# display_driver.net
KiCad netlist of a schematic drawn in EAGLE
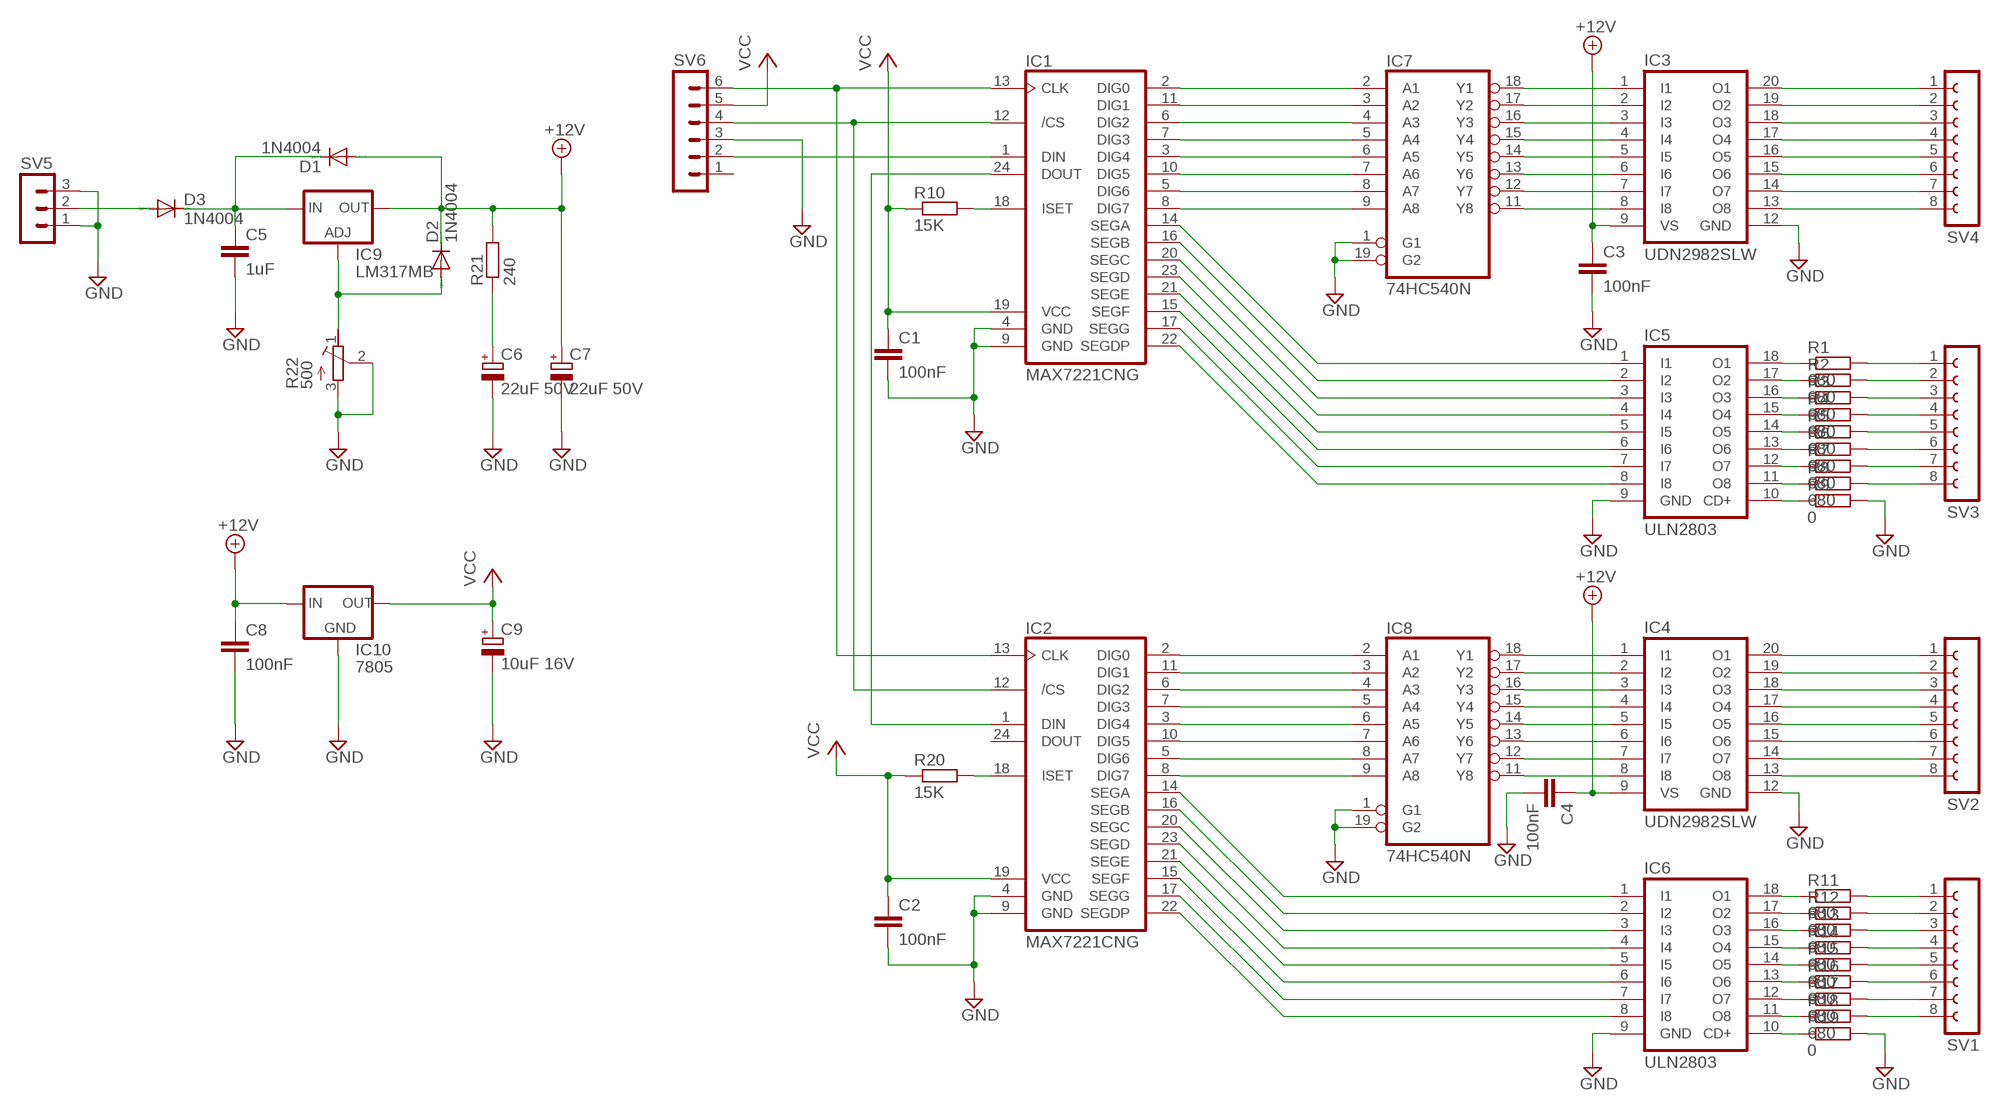
[diagram p0: schematic, sheet 1]

(export (version "E")
  (design (tool "Eeschema 10.0.6"))
  (components
    (comp (ref "C1")
      (value "100nF")
      (footprint "eagle-import:C5B2.5")
      (libsource (lib "eagle-import") (part "C5/2.5"))
    )
    (comp (ref "C2")
      (value "100nF")
      (footprint "eagle-import:C5B2.5")
      (libsource (lib "eagle-import") (part "C5/2.5"))
    )
    (comp (ref "C3")
      (value "100nF")
      (footprint "eagle-import:C5B2.5")
      (libsource (lib "eagle-import") (part "C5/2.5"))
    )
    (comp (ref "C4")
      (value "100nF")
      (footprint "eagle-import:C5B2.5")
      (libsource (lib "eagle-import") (part "C5/2.5"))
    )
    (comp (ref "C5")
      (value "1uF")
      (footprint "eagle-import:C5B2.5")
      (libsource (lib "eagle-import") (part "C5/2.5"))
    )
    (comp (ref "C6")
      (value "22uF 50V")
      (footprint "eagle-import:E3,5-8")
      (libsource (lib "eagle-import") (part "CPOL-EUE3.5-8"))
    )
    (comp (ref "C7")
      (value "22uF 50V")
      (footprint "eagle-import:E3,5-8")
      (libsource (lib "eagle-import") (part "CPOL-EUE3.5-8"))
    )
    (comp (ref "C8")
      (value "100nF")
      (footprint "eagle-import:C5B2.5")
      (libsource (lib "eagle-import") (part "C5/2.5"))
    )
    (comp (ref "C9")
      (value "10uF 16V")
      (footprint "eagle-import:E3,5-8")
      (libsource (lib "eagle-import") (part "CPOL-EUE3.5-8"))
    )
    (comp (ref "D1")
      (value "1N4004")
      (footprint "eagle-import:DO41-10")
      (libsource (lib "eagle-import") (part "1N4004"))
    )
    (comp (ref "D2")
      (value "1N4004")
      (footprint "eagle-import:DO41-10")
      (libsource (lib "eagle-import") (part "1N4004"))
    )
    (comp (ref "D3")
      (value "1N4004")
      (footprint "eagle-import:DO41-10")
      (libsource (lib "eagle-import") (part "1N4004"))
    )
    (comp (ref "IC1")
      (value "MAX7221CNG")
      (footprint "eagle-import:DIL24-3")
      (libsource (lib "eagle-import") (part "MAX7221NGC"))
    )
    (comp (ref "IC2")
      (value "MAX7221CNG")
      (footprint "eagle-import:DIL24-3")
      (libsource (lib "eagle-import") (part "MAX7221NGC"))
    )
    (comp (ref "IC3")
      (value "UDN2982SLW")
      (footprint "eagle-import:SO20W")
      (libsource (lib "eagle-import") (part "UDN298SLW2"))
    )
    (comp (ref "IC4")
      (value "UDN2982SLW")
      (footprint "eagle-import:SO20W")
      (libsource (lib "eagle-import") (part "UDN298SLW2"))
    )
    (comp (ref "IC5")
      (value "ULN2803")
      (footprint "eagle-import:DIL18")
      (libsource (lib "eagle-import") (part "ULN2803A"))
    )
    (comp (ref "IC6")
      (value "ULN2803")
      (footprint "eagle-import:DIL18")
      (libsource (lib "eagle-import") (part "ULN2803A"))
    )
    (comp (ref "IC7")
      (value "74HC540N")
      (footprint "eagle-import:DIL20")
      (libsource (lib "eagle-import") (part "74540NHC"))
    )
    (comp (ref "IC8")
      (value "74HC540N")
      (footprint "eagle-import:DIL20")
      (libsource (lib "eagle-import") (part "74540NHC"))
    )
    (comp (ref "IC9")
      (value "LM317MB")
      (footprint "eagle-import:TO220L1")
      (libsource (lib "eagle-import") (part "LM317?MB"))
    )
    (comp (ref "IC10")
      (value "7805")
      (footprint "eagle-import:78XXL")
      (libsource (lib "eagle-import") (part "78XXL"))
    )
    (comp (ref "R1")
      (value "680")
      (footprint "eagle-import:0207_10")
      (libsource (lib "eagle-import") (part "R-EU_0207/10"))
    )
    (comp (ref "R2")
      (value "680")
      (footprint "eagle-import:0207_10")
      (libsource (lib "eagle-import") (part "R-EU_0207/10"))
    )
    (comp (ref "R3")
      (value "680")
      (footprint "eagle-import:0207_10")
      (libsource (lib "eagle-import") (part "R-EU_0207/10"))
    )
    (comp (ref "R4")
      (value "680")
      (footprint "eagle-import:0207_10")
      (libsource (lib "eagle-import") (part "R-EU_0207/10"))
    )
    (comp (ref "R5")
      (value "680")
      (footprint "eagle-import:0207_10")
      (libsource (lib "eagle-import") (part "R-EU_0207/10"))
    )
    (comp (ref "R6")
      (value "680")
      (footprint "eagle-import:0207_10")
      (libsource (lib "eagle-import") (part "R-EU_0207/10"))
    )
    (comp (ref "R7")
      (value "680")
      (footprint "eagle-import:0207_10")
      (libsource (lib "eagle-import") (part "R-EU_0207/10"))
    )
    (comp (ref "R8")
      (value "680")
      (footprint "eagle-import:0207_10")
      (libsource (lib "eagle-import") (part "R-EU_0207/10"))
    )
    (comp (ref "R9")
      (value "0")
      (footprint "eagle-import:0207_10")
      (libsource (lib "eagle-import") (part "R-EU_0207/10"))
    )
    (comp (ref "R10")
      (value "15K")
      (footprint "eagle-import:0207_10")
      (libsource (lib "eagle-import") (part "R-EU_0207/10"))
    )
    (comp (ref "R11")
      (value "680")
      (footprint "eagle-import:0207_10")
      (libsource (lib "eagle-import") (part "R-EU_0207/10"))
    )
    (comp (ref "R12")
      (value "680")
      (footprint "eagle-import:0207_10")
      (libsource (lib "eagle-import") (part "R-EU_0207/10"))
    )
    (comp (ref "R13")
      (value "680")
      (footprint "eagle-import:0207_10")
      (libsource (lib "eagle-import") (part "R-EU_0207/10"))
    )
    (comp (ref "R14")
      (value "680")
      (footprint "eagle-import:0207_10")
      (libsource (lib "eagle-import") (part "R-EU_0207/10"))
    )
    (comp (ref "R15")
      (value "680")
      (footprint "eagle-import:0207_10")
      (libsource (lib "eagle-import") (part "R-EU_0207/10"))
    )
    (comp (ref "R16")
      (value "680")
      (footprint "eagle-import:0207_10")
      (libsource (lib "eagle-import") (part "R-EU_0207/10"))
    )
    (comp (ref "R17")
      (value "680")
      (footprint "eagle-import:0207_10")
      (libsource (lib "eagle-import") (part "R-EU_0207/10"))
    )
    (comp (ref "R18")
      (value "680")
      (footprint "eagle-import:0207_10")
      (libsource (lib "eagle-import") (part "R-EU_0207/10"))
    )
    (comp (ref "R19")
      (value "0")
      (footprint "eagle-import:0207_10")
      (libsource (lib "eagle-import") (part "R-EU_0207/10"))
    )
    (comp (ref "R20")
      (value "15K")
      (footprint "eagle-import:0207_10")
      (libsource (lib "eagle-import") (part "R-EU_0207/10"))
    )
    (comp (ref "R21")
      (value "240")
      (footprint "eagle-import:0207_10")
      (libsource (lib "eagle-import") (part "R-EU_0207/10"))
    )
    (comp (ref "R22")
      (value "500")
      (footprint "eagle-import:RTRIMT93YA")
      (libsource (lib "eagle-import") (part "R-TRIMMT93YA"))
    )
    (comp (ref "SV1")
      (value "FE08-1")
      (footprint "eagle-import:FE08")
      (libsource (lib "eagle-import") (part "FE08-1"))
    )
    (comp (ref "SV2")
      (value "FE08-1")
      (footprint "eagle-import:FE08")
      (libsource (lib "eagle-import") (part "FE08-1"))
    )
    (comp (ref "SV3")
      (value "FE08-1")
      (footprint "eagle-import:FE08")
      (libsource (lib "eagle-import") (part "FE08-1"))
    )
    (comp (ref "SV4")
      (value "FE08-1")
      (footprint "eagle-import:FE08")
      (libsource (lib "eagle-import") (part "FE08-1"))
    )
    (comp (ref "SV5")
      (value "MA03-1")
      (footprint "eagle-import:MA03-1")
      (libsource (lib "eagle-import") (part "MA03-1"))
    )
    (comp (ref "SV6")
      (value "MA06-1")
      (footprint "eagle-import:MA06-1")
      (libsource (lib "eagle-import") (part "MA06-1"))
    )
  )
  (nets
    (net (code "1") (name "+12V") (class "Default")
      (node (ref "C3") (pin "1") (pinfunction "1_1") (pintype "passive"))
      (node (ref "C4") (pin "1") (pinfunction "1_1") (pintype "passive"))
      (node (ref "C7") (pin "+") (pinfunction "+_+") (pintype "passive"))
      (node (ref "C8") (pin "1") (pinfunction "1_1") (pintype "passive"))
      (node (ref "D1") (pin "A") (pinfunction "A_A") (pintype "passive"))
      (node (ref "D2") (pin "C") (pinfunction "C_C") (pintype "passive"))
      (node (ref "IC10") (pin "IN") (pinfunction "IN_IN") (pintype "input"))
      (node (ref "IC3") (pin "9") (pinfunction "VS_9") (pintype "passive"))
      (node (ref "IC4") (pin "9") (pinfunction "VS_9") (pintype "passive"))
      (node (ref "IC9") (pin "2") (pinfunction "OUT_2") (pintype "passive"))
      (node (ref "R21") (pin "2") (pinfunction "2_2") (pintype "passive"))
    )
    (net (code "2") (name "GND") (class "Default")
      (node (ref "C1") (pin "2") (pinfunction "2_2") (pintype "passive"))
      (node (ref "C2") (pin "2") (pinfunction "2_2") (pintype "passive"))
      (node (ref "C3") (pin "2") (pinfunction "2_2") (pintype "passive"))
      (node (ref "C4") (pin "2") (pinfunction "2_2") (pintype "passive"))
      (node (ref "C5") (pin "2") (pinfunction "2_2") (pintype "passive"))
      (node (ref "C6") (pin "-") (pinfunction "-_-") (pintype "passive"))
      (node (ref "C7") (pin "-") (pinfunction "-_-") (pintype "passive"))
      (node (ref "C8") (pin "2") (pinfunction "2_2") (pintype "passive"))
      (node (ref "C9") (pin "-") (pinfunction "-_-") (pintype "passive"))
      (node (ref "IC1") (pin "4") (pinfunction "GND_4") (pintype "power_in"))
      (node (ref "IC1") (pin "9") (pinfunction "GND_9") (pintype "power_in"))
      (node (ref "IC10") (pin "GND") (pinfunction "GND_GND") (pintype "input"))
      (node (ref "IC2") (pin "4") (pinfunction "GND_4") (pintype "power_in"))
      (node (ref "IC2") (pin "9") (pinfunction "GND_9") (pintype "power_in"))
      (node (ref "IC3") (pin "12") (pinfunction "GND_12") (pintype "power_in"))
      (node (ref "IC4") (pin "12") (pinfunction "GND_12") (pintype "power_in"))
      (node (ref "IC5") (pin "9") (pinfunction "GND_9") (pintype "power_in"))
      (node (ref "IC6") (pin "9") (pinfunction "GND_9") (pintype "power_in"))
      (node (ref "IC7") (pin "1") (pinfunction "G1_1") (pintype "input"))
      (node (ref "IC7") (pin "19") (pinfunction "G2_19") (pintype "input"))
      (node (ref "IC8") (pin "1") (pinfunction "G1_1") (pintype "input"))
      (node (ref "IC8") (pin "19") (pinfunction "G2_19") (pintype "input"))
      (node (ref "R19") (pin "2") (pinfunction "2_2") (pintype "passive"))
      (node (ref "R22") (pin "2") (pinfunction "S_2") (pintype "passive"))
      (node (ref "R22") (pin "3") (pinfunction "A_3") (pintype "passive"))
      (node (ref "R9") (pin "2") (pinfunction "2_2") (pintype "passive"))
      (node (ref "SV5") (pin "1") (pinfunction "1_1") (pintype "passive"))
      (node (ref "SV5") (pin "3") (pinfunction "3_3") (pintype "passive"))
      (node (ref "SV6") (pin "3") (pinfunction "3_3") (pintype "passive"))
    )
    (net (code "3") (name "Net-(C6-Pad+)") (class "Default")
      (node (ref "C6") (pin "+") (pinfunction "+_+") (pintype "passive"))
      (node (ref "R21") (pin "1") (pinfunction "1_1") (pintype "passive"))
    )
    (net (code "4") (name "Net-(D3-PadA)") (class "Default")
      (node (ref "D3") (pin "A") (pinfunction "A_A") (pintype "passive"))
      (node (ref "SV5") (pin "2") (pinfunction "2_2") (pintype "passive"))
    )
    (net (code "5") (name "Net-(IC1-CLK)") (class "Default")
      (node (ref "IC1") (pin "13") (pinfunction "CLK_13") (pintype "input"))
      (node (ref "IC2") (pin "13") (pinfunction "CLK_13") (pintype "input"))
      (node (ref "SV6") (pin "6") (pinfunction "6_6") (pintype "passive"))
    )
    (net (code "6") (name "Net-(IC1-DIG0)") (class "Default")
      (node (ref "IC1") (pin "2") (pinfunction "DIG0_2") (pintype "open_collector"))
      (node (ref "IC7") (pin "2") (pinfunction "A1_2") (pintype "input"))
    )
    (net (code "7") (name "Net-(IC1-DIG1)") (class "Default")
      (node (ref "IC1") (pin "11") (pinfunction "DIG1_11") (pintype "open_collector"))
      (node (ref "IC7") (pin "3") (pinfunction "A2_3") (pintype "input"))
    )
    (net (code "8") (name "Net-(IC1-DIG2)") (class "Default")
      (node (ref "IC1") (pin "6") (pinfunction "DIG2_6") (pintype "open_collector"))
      (node (ref "IC7") (pin "4") (pinfunction "A3_4") (pintype "input"))
    )
    (net (code "9") (name "Net-(IC1-DIG3)") (class "Default")
      (node (ref "IC1") (pin "7") (pinfunction "DIG3_7") (pintype "open_collector"))
      (node (ref "IC7") (pin "5") (pinfunction "A4_5") (pintype "input"))
    )
    (net (code "10") (name "Net-(IC1-DIG4)") (class "Default")
      (node (ref "IC1") (pin "3") (pinfunction "DIG4_3") (pintype "open_collector"))
      (node (ref "IC7") (pin "6") (pinfunction "A5_6") (pintype "input"))
    )
    (net (code "11") (name "Net-(IC1-DIG5)") (class "Default")
      (node (ref "IC1") (pin "10") (pinfunction "DIG5_10") (pintype "open_collector"))
      (node (ref "IC7") (pin "7") (pinfunction "A6_7") (pintype "input"))
    )
    (net (code "12") (name "Net-(IC1-DIG6)") (class "Default")
      (node (ref "IC1") (pin "5") (pinfunction "DIG6_5") (pintype "open_collector"))
      (node (ref "IC7") (pin "8") (pinfunction "A7_8") (pintype "input"))
    )
    (net (code "13") (name "Net-(IC1-DIG7)") (class "Default")
      (node (ref "IC1") (pin "8") (pinfunction "DIG7_8") (pintype "open_collector"))
      (node (ref "IC7") (pin "9") (pinfunction "A8_9") (pintype "input"))
    )
    (net (code "14") (name "Net-(IC1-DIN)") (class "Default")
      (node (ref "IC1") (pin "1") (pinfunction "DIN_1") (pintype "input"))
      (node (ref "SV6") (pin "2") (pinfunction "2_2") (pintype "passive"))
    )
    (net (code "15") (name "Net-(IC1-DOUT)") (class "Default")
      (node (ref "IC1") (pin "24") (pinfunction "DOUT_24") (pintype "output"))
      (node (ref "IC2") (pin "1") (pinfunction "DIN_1") (pintype "input"))
    )
    (net (code "16") (name "Net-(IC1-ISET)") (class "Default")
      (node (ref "IC1") (pin "18") (pinfunction "ISET_18") (pintype "input"))
      (node (ref "R10") (pin "2") (pinfunction "2_2") (pintype "passive"))
    )
    (net (code "17") (name "Net-(IC1-SEGA)") (class "Default")
      (node (ref "IC1") (pin "14") (pinfunction "SEGA_14") (pintype "output"))
      (node (ref "IC5") (pin "1") (pinfunction "I1_1") (pintype "input"))
    )
    (net (code "18") (name "Net-(IC1-SEGB)") (class "Default")
      (node (ref "IC1") (pin "16") (pinfunction "SEGB_16") (pintype "output"))
      (node (ref "IC5") (pin "2") (pinfunction "I2_2") (pintype "input"))
    )
    (net (code "19") (name "Net-(IC1-SEGC)") (class "Default")
      (node (ref "IC1") (pin "20") (pinfunction "SEGC_20") (pintype "output"))
      (node (ref "IC5") (pin "3") (pinfunction "I3_3") (pintype "input"))
    )
    (net (code "20") (name "Net-(IC1-SEGD)") (class "Default")
      (node (ref "IC1") (pin "23") (pinfunction "SEGD_23") (pintype "output"))
      (node (ref "IC5") (pin "4") (pinfunction "I4_4") (pintype "input"))
    )
    (net (code "21") (name "Net-(IC1-SEGDP)") (class "Default")
      (node (ref "IC1") (pin "22") (pinfunction "SEGDP_22") (pintype "output"))
      (node (ref "IC5") (pin "8") (pinfunction "I8_8") (pintype "input"))
    )
    (net (code "22") (name "Net-(IC1-SEGE)") (class "Default")
      (node (ref "IC1") (pin "21") (pinfunction "SEGE_21") (pintype "output"))
      (node (ref "IC5") (pin "5") (pinfunction "I5_5") (pintype "input"))
    )
    (net (code "23") (name "Net-(IC1-SEGF)") (class "Default")
      (node (ref "IC1") (pin "15") (pinfunction "SEGF_15") (pintype "output"))
      (node (ref "IC5") (pin "6") (pinfunction "I6_6") (pintype "input"))
    )
    (net (code "24") (name "Net-(IC1-SEGG)") (class "Default")
      (node (ref "IC1") (pin "17") (pinfunction "SEGG_17") (pintype "output"))
      (node (ref "IC5") (pin "7") (pinfunction "I7_7") (pintype "input"))
    )
    (net (code "25") (name "Net-(IC1-{slash}CS)") (class "Default")
      (node (ref "IC1") (pin "12") (pinfunction "/CS_12") (pintype "input"))
      (node (ref "IC2") (pin "12") (pinfunction "/CS_12") (pintype "input"))
      (node (ref "SV6") (pin "4") (pinfunction "4_4") (pintype "passive"))
    )
    (net (code "26") (name "Net-(IC2-DIG0)") (class "Default")
      (node (ref "IC2") (pin "2") (pinfunction "DIG0_2") (pintype "open_collector"))
      (node (ref "IC8") (pin "2") (pinfunction "A1_2") (pintype "input"))
    )
    (net (code "27") (name "Net-(IC2-DIG1)") (class "Default")
      (node (ref "IC2") (pin "11") (pinfunction "DIG1_11") (pintype "open_collector"))
      (node (ref "IC8") (pin "3") (pinfunction "A2_3") (pintype "input"))
    )
    (net (code "28") (name "Net-(IC2-DIG2)") (class "Default")
      (node (ref "IC2") (pin "6") (pinfunction "DIG2_6") (pintype "open_collector"))
      (node (ref "IC8") (pin "4") (pinfunction "A3_4") (pintype "input"))
    )
    (net (code "29") (name "Net-(IC2-DIG3)") (class "Default")
      (node (ref "IC2") (pin "7") (pinfunction "DIG3_7") (pintype "open_collector"))
      (node (ref "IC8") (pin "5") (pinfunction "A4_5") (pintype "input"))
    )
    (net (code "30") (name "Net-(IC2-DIG4)") (class "Default")
      (node (ref "IC2") (pin "3") (pinfunction "DIG4_3") (pintype "open_collector"))
      (node (ref "IC8") (pin "6") (pinfunction "A5_6") (pintype "input"))
    )
    (net (code "31") (name "Net-(IC2-DIG5)") (class "Default")
      (node (ref "IC2") (pin "10") (pinfunction "DIG5_10") (pintype "open_collector"))
      (node (ref "IC8") (pin "7") (pinfunction "A6_7") (pintype "input"))
    )
    (net (code "32") (name "Net-(IC2-DIG6)") (class "Default")
      (node (ref "IC2") (pin "5") (pinfunction "DIG6_5") (pintype "open_collector"))
      (node (ref "IC8") (pin "8") (pinfunction "A7_8") (pintype "input"))
    )
    (net (code "33") (name "Net-(IC2-DIG7)") (class "Default")
      (node (ref "IC2") (pin "8") (pinfunction "DIG7_8") (pintype "open_collector"))
      (node (ref "IC8") (pin "9") (pinfunction "A8_9") (pintype "input"))
    )
    (net (code "34") (name "Net-(IC2-ISET)") (class "Default")
      (node (ref "IC2") (pin "18") (pinfunction "ISET_18") (pintype "input"))
      (node (ref "R20") (pin "2") (pinfunction "2_2") (pintype "passive"))
    )
    (net (code "35") (name "Net-(IC2-SEGA)") (class "Default")
      (node (ref "IC2") (pin "14") (pinfunction "SEGA_14") (pintype "output"))
      (node (ref "IC6") (pin "1") (pinfunction "I1_1") (pintype "input"))
    )
    (net (code "36") (name "Net-(IC2-SEGB)") (class "Default")
      (node (ref "IC2") (pin "16") (pinfunction "SEGB_16") (pintype "output"))
      (node (ref "IC6") (pin "2") (pinfunction "I2_2") (pintype "input"))
    )
    (net (code "37") (name "Net-(IC2-SEGC)") (class "Default")
      (node (ref "IC2") (pin "20") (pinfunction "SEGC_20") (pintype "output"))
      (node (ref "IC6") (pin "3") (pinfunction "I3_3") (pintype "input"))
    )
    (net (code "38") (name "Net-(IC2-SEGD)") (class "Default")
      (node (ref "IC2") (pin "23") (pinfunction "SEGD_23") (pintype "output"))
      (node (ref "IC6") (pin "4") (pinfunction "I4_4") (pintype "input"))
    )
    (net (code "39") (name "Net-(IC2-SEGDP)") (class "Default")
      (node (ref "IC2") (pin "22") (pinfunction "SEGDP_22") (pintype "output"))
      (node (ref "IC6") (pin "8") (pinfunction "I8_8") (pintype "input"))
    )
    (net (code "40") (name "Net-(IC2-SEGE)") (class "Default")
      (node (ref "IC2") (pin "21") (pinfunction "SEGE_21") (pintype "output"))
      (node (ref "IC6") (pin "5") (pinfunction "I5_5") (pintype "input"))
    )
    (net (code "41") (name "Net-(IC2-SEGF)") (class "Default")
      (node (ref "IC2") (pin "15") (pinfunction "SEGF_15") (pintype "output"))
      (node (ref "IC6") (pin "6") (pinfunction "I6_6") (pintype "input"))
    )
    (net (code "42") (name "Net-(IC2-SEGG)") (class "Default")
      (node (ref "IC2") (pin "17") (pinfunction "SEGG_17") (pintype "output"))
      (node (ref "IC6") (pin "7") (pinfunction "I7_7") (pintype "input"))
    )
    (net (code "43") (name "Net-(IC3-I1)") (class "Default")
      (node (ref "IC3") (pin "1") (pinfunction "I1_1") (pintype "input"))
      (node (ref "IC7") (pin "18") (pinfunction "Y1_18") (pintype "tri_state"))
    )
    (net (code "44") (name "Net-(IC3-I2)") (class "Default")
      (node (ref "IC3") (pin "2") (pinfunction "I2_2") (pintype "input"))
      (node (ref "IC7") (pin "17") (pinfunction "Y2_17") (pintype "tri_state"))
    )
    (net (code "45") (name "Net-(IC3-I3)") (class "Default")
      (node (ref "IC3") (pin "3") (pinfunction "I3_3") (pintype "input"))
      (node (ref "IC7") (pin "16") (pinfunction "Y3_16") (pintype "tri_state"))
    )
    (net (code "46") (name "Net-(IC3-I4)") (class "Default")
      (node (ref "IC3") (pin "4") (pinfunction "I4_4") (pintype "input"))
      (node (ref "IC7") (pin "15") (pinfunction "Y4_15") (pintype "tri_state"))
    )
    (net (code "47") (name "Net-(IC3-I5)") (class "Default")
      (node (ref "IC3") (pin "5") (pinfunction "I5_5") (pintype "input"))
      (node (ref "IC7") (pin "14") (pinfunction "Y5_14") (pintype "tri_state"))
    )
    (net (code "48") (name "Net-(IC3-I6)") (class "Default")
      (node (ref "IC3") (pin "6") (pinfunction "I6_6") (pintype "input"))
      (node (ref "IC7") (pin "13") (pinfunction "Y6_13") (pintype "tri_state"))
    )
    (net (code "49") (name "Net-(IC3-I7)") (class "Default")
      (node (ref "IC3") (pin "7") (pinfunction "I7_7") (pintype "input"))
      (node (ref "IC7") (pin "12") (pinfunction "Y7_12") (pintype "tri_state"))
    )
    (net (code "50") (name "Net-(IC3-I8)") (class "Default")
      (node (ref "IC3") (pin "8") (pinfunction "I8_8") (pintype "input"))
      (node (ref "IC7") (pin "11") (pinfunction "Y8_11") (pintype "tri_state"))
    )
    (net (code "51") (name "Net-(IC3-O1)") (class "Default")
      (node (ref "IC3") (pin "20") (pinfunction "O1_20") (pintype "open_collector"))
      (node (ref "SV4") (pin "1") (pinfunction "1_1") (pintype "passive"))
    )
    (net (code "52") (name "Net-(IC3-O2)") (class "Default")
      (node (ref "IC3") (pin "19") (pinfunction "O2_19") (pintype "open_collector"))
      (node (ref "SV4") (pin "2") (pinfunction "2_2") (pintype "passive"))
    )
    (net (code "53") (name "Net-(IC3-O3)") (class "Default")
      (node (ref "IC3") (pin "18") (pinfunction "O3_18") (pintype "open_collector"))
      (node (ref "SV4") (pin "3") (pinfunction "3_3") (pintype "passive"))
    )
    (net (code "54") (name "Net-(IC3-O4)") (class "Default")
      (node (ref "IC3") (pin "17") (pinfunction "O4_17") (pintype "open_collector"))
      (node (ref "SV4") (pin "4") (pinfunction "4_4") (pintype "passive"))
    )
    (net (code "55") (name "Net-(IC3-O5)") (class "Default")
      (node (ref "IC3") (pin "16") (pinfunction "O5_16") (pintype "open_collector"))
      (node (ref "SV4") (pin "5") (pinfunction "5_5") (pintype "passive"))
    )
    (net (code "56") (name "Net-(IC3-O6)") (class "Default")
      (node (ref "IC3") (pin "15") (pinfunction "O6_15") (pintype "open_collector"))
      (node (ref "SV4") (pin "6") (pinfunction "6_6") (pintype "passive"))
    )
    (net (code "57") (name "Net-(IC3-O7)") (class "Default")
      (node (ref "IC3") (pin "14") (pinfunction "O7_14") (pintype "open_collector"))
      (node (ref "SV4") (pin "7") (pinfunction "7_7") (pintype "passive"))
    )
    (net (code "58") (name "Net-(IC3-O8)") (class "Default")
      (node (ref "IC3") (pin "13") (pinfunction "O8_13") (pintype "open_collector"))
      (node (ref "SV4") (pin "8") (pinfunction "8_8") (pintype "passive"))
    )
    (net (code "59") (name "Net-(IC4-I1)") (class "Default")
      (node (ref "IC4") (pin "1") (pinfunction "I1_1") (pintype "input"))
      (node (ref "IC8") (pin "18") (pinfunction "Y1_18") (pintype "tri_state"))
    )
    (net (code "60") (name "Net-(IC4-I2)") (class "Default")
      (node (ref "IC4") (pin "2") (pinfunction "I2_2") (pintype "input"))
      (node (ref "IC8") (pin "17") (pinfunction "Y2_17") (pintype "tri_state"))
    )
    (net (code "61") (name "Net-(IC4-I3)") (class "Default")
      (node (ref "IC4") (pin "3") (pinfunction "I3_3") (pintype "input"))
      (node (ref "IC8") (pin "16") (pinfunction "Y3_16") (pintype "tri_state"))
    )
    (net (code "62") (name "Net-(IC4-I4)") (class "Default")
      (node (ref "IC4") (pin "4") (pinfunction "I4_4") (pintype "input"))
      (node (ref "IC8") (pin "15") (pinfunction "Y4_15") (pintype "tri_state"))
    )
    (net (code "63") (name "Net-(IC4-I5)") (class "Default")
      (node (ref "IC4") (pin "5") (pinfunction "I5_5") (pintype "input"))
      (node (ref "IC8") (pin "14") (pinfunction "Y5_14") (pintype "tri_state"))
    )
    (net (code "64") (name "Net-(IC4-I6)") (class "Default")
      (node (ref "IC4") (pin "6") (pinfunction "I6_6") (pintype "input"))
      (node (ref "IC8") (pin "13") (pinfunction "Y6_13") (pintype "tri_state"))
    )
    (net (code "65") (name "Net-(IC4-I7)") (class "Default")
      (node (ref "IC4") (pin "7") (pinfunction "I7_7") (pintype "input"))
      (node (ref "IC8") (pin "12") (pinfunction "Y7_12") (pintype "tri_state"))
    )
    (net (code "66") (name "Net-(IC4-I8)") (class "Default")
      (node (ref "IC4") (pin "8") (pinfunction "I8_8") (pintype "input"))
      (node (ref "IC8") (pin "11") (pinfunction "Y8_11") (pintype "tri_state"))
    )
    (net (code "67") (name "Net-(IC4-O1)") (class "Default")
      (node (ref "IC4") (pin "20") (pinfunction "O1_20") (pintype "open_collector"))
      (node (ref "SV2") (pin "1") (pinfunction "1_1") (pintype "passive"))
    )
    (net (code "68") (name "Net-(IC4-O2)") (class "Default")
      (node (ref "IC4") (pin "19") (pinfunction "O2_19") (pintype "open_collector"))
      (node (ref "SV2") (pin "2") (pinfunction "2_2") (pintype "passive"))
    )
    (net (code "69") (name "Net-(IC4-O3)") (class "Default")
      (node (ref "IC4") (pin "18") (pinfunction "O3_18") (pintype "open_collector"))
      (node (ref "SV2") (pin "3") (pinfunction "3_3") (pintype "passive"))
    )
    (net (code "70") (name "Net-(IC4-O4)") (class "Default")
      (node (ref "IC4") (pin "17") (pinfunction "O4_17") (pintype "open_collector"))
      (node (ref "SV2") (pin "4") (pinfunction "4_4") (pintype "passive"))
    )
    (net (code "71") (name "Net-(IC4-O5)") (class "Default")
      (node (ref "IC4") (pin "16") (pinfunction "O5_16") (pintype "open_collector"))
      (node (ref "SV2") (pin "5") (pinfunction "5_5") (pintype "passive"))
    )
    (net (code "72") (name "Net-(IC4-O6)") (class "Default")
      (node (ref "IC4") (pin "15") (pinfunction "O6_15") (pintype "open_collector"))
      (node (ref "SV2") (pin "6") (pinfunction "6_6") (pintype "passive"))
    )
    (net (code "73") (name "Net-(IC4-O7)") (class "Default")
      (node (ref "IC4") (pin "14") (pinfunction "O7_14") (pintype "open_collector"))
      (node (ref "SV2") (pin "7") (pinfunction "7_7") (pintype "passive"))
    )
    (net (code "74") (name "Net-(IC4-O8)") (class "Default")
      (node (ref "IC4") (pin "13") (pinfunction "O8_13") (pintype "open_collector"))
      (node (ref "SV2") (pin "8") (pinfunction "8_8") (pintype "passive"))
    )
    (net (code "75") (name "Net-(IC5-CD+)") (class "Default")
      (node (ref "IC5") (pin "10") (pinfunction "CD+_10") (pintype "passive"))
      (node (ref "R9") (pin "1") (pinfunction "1_1") (pintype "passive"))
    )
    (net (code "76") (name "Net-(IC5-O1)") (class "Default")
      (node (ref "IC5") (pin "18") (pinfunction "O1_18") (pintype "open_collector"))
      (node (ref "R1") (pin "1") (pinfunction "1_1") (pintype "passive"))
    )
    (net (code "77") (name "Net-(IC5-O2)") (class "Default")
      (node (ref "IC5") (pin "17") (pinfunction "O2_17") (pintype "open_collector"))
      (node (ref "R2") (pin "1") (pinfunction "1_1") (pintype "passive"))
    )
    (net (code "78") (name "Net-(IC5-O3)") (class "Default")
      (node (ref "IC5") (pin "16") (pinfunction "O3_16") (pintype "open_collector"))
      (node (ref "R3") (pin "1") (pinfunction "1_1") (pintype "passive"))
    )
    (net (code "79") (name "Net-(IC5-O4)") (class "Default")
      (node (ref "IC5") (pin "15") (pinfunction "O4_15") (pintype "open_collector"))
      (node (ref "R4") (pin "1") (pinfunction "1_1") (pintype "passive"))
    )
    (net (code "80") (name "Net-(IC5-O5)") (class "Default")
      (node (ref "IC5") (pin "14") (pinfunction "O5_14") (pintype "open_collector"))
      (node (ref "R5") (pin "1") (pinfunction "1_1") (pintype "passive"))
    )
    (net (code "81") (name "Net-(IC5-O6)") (class "Default")
      (node (ref "IC5") (pin "13") (pinfunction "O6_13") (pintype "open_collector"))
      (node (ref "R6") (pin "1") (pinfunction "1_1") (pintype "passive"))
    )
    (net (code "82") (name "Net-(IC5-O7)") (class "Default")
      (node (ref "IC5") (pin "12") (pinfunction "O7_12") (pintype "open_collector"))
      (node (ref "R7") (pin "1") (pinfunction "1_1") (pintype "passive"))
    )
    (net (code "83") (name "Net-(IC5-O8)") (class "Default")
      (node (ref "IC5") (pin "11") (pinfunction "O8_11") (pintype "open_collector"))
      (node (ref "R8") (pin "1") (pinfunction "1_1") (pintype "passive"))
    )
    (net (code "84") (name "Net-(IC6-CD+)") (class "Default")
      (node (ref "IC6") (pin "10") (pinfunction "CD+_10") (pintype "passive"))
      (node (ref "R19") (pin "1") (pinfunction "1_1") (pintype "passive"))
    )
    (net (code "85") (name "Net-(IC6-O1)") (class "Default")
      (node (ref "IC6") (pin "18") (pinfunction "O1_18") (pintype "open_collector"))
      (node (ref "R11") (pin "1") (pinfunction "1_1") (pintype "passive"))
    )
    (net (code "86") (name "Net-(IC6-O2)") (class "Default")
      (node (ref "IC6") (pin "17") (pinfunction "O2_17") (pintype "open_collector"))
      (node (ref "R12") (pin "1") (pinfunction "1_1") (pintype "passive"))
    )
    (net (code "87") (name "Net-(IC6-O3)") (class "Default")
      (node (ref "IC6") (pin "16") (pinfunction "O3_16") (pintype "open_collector"))
      (node (ref "R13") (pin "1") (pinfunction "1_1") (pintype "passive"))
    )
    (net (code "88") (name "Net-(IC6-O4)") (class "Default")
      (node (ref "IC6") (pin "15") (pinfunction "O4_15") (pintype "open_collector"))
      (node (ref "R14") (pin "1") (pinfunction "1_1") (pintype "passive"))
    )
    (net (code "89") (name "Net-(IC6-O5)") (class "Default")
      (node (ref "IC6") (pin "14") (pinfunction "O5_14") (pintype "open_collector"))
      (node (ref "R15") (pin "1") (pinfunction "1_1") (pintype "passive"))
    )
    (net (code "90") (name "Net-(IC6-O6)") (class "Default")
      (node (ref "IC6") (pin "13") (pinfunction "O6_13") (pintype "open_collector"))
      (node (ref "R16") (pin "1") (pinfunction "1_1") (pintype "passive"))
    )
    (net (code "91") (name "Net-(IC6-O7)") (class "Default")
      (node (ref "IC6") (pin "12") (pinfunction "O7_12") (pintype "open_collector"))
      (node (ref "R17") (pin "1") (pinfunction "1_1") (pintype "passive"))
    )
    (net (code "92") (name "Net-(IC6-O8)") (class "Default")
      (node (ref "IC6") (pin "11") (pinfunction "O8_11") (pintype "open_collector"))
      (node (ref "R18") (pin "1") (pinfunction "1_1") (pintype "passive"))
    )
    (net (code "93") (name "Net-(IC9-ADJ)") (class "Default")
      (node (ref "D2") (pin "A") (pinfunction "A_A") (pintype "passive"))
      (node (ref "IC9") (pin "1") (pinfunction "ADJ_1") (pintype "input"))
      (node (ref "R22") (pin "1") (pinfunction "E_1") (pintype "passive"))
    )
    (net (code "94") (name "Net-(IC9-IN)") (class "Default")
      (node (ref "C5") (pin "1") (pinfunction "1_1") (pintype "passive"))
      (node (ref "D1") (pin "C") (pinfunction "C_C") (pintype "passive"))
      (node (ref "D3") (pin "C") (pinfunction "C_C") (pintype "passive"))
      (node (ref "IC9") (pin "3") (pinfunction "IN_3") (pintype "input"))
    )
    (net (code "95") (name "Net-(R1-Pad2)") (class "Default")
      (node (ref "R1") (pin "2") (pinfunction "2_2") (pintype "passive"))
      (node (ref "SV3") (pin "1") (pinfunction "1_1") (pintype "passive"))
    )
    (net (code "96") (name "Net-(R2-Pad2)") (class "Default")
      (node (ref "R2") (pin "2") (pinfunction "2_2") (pintype "passive"))
      (node (ref "SV3") (pin "2") (pinfunction "2_2") (pintype "passive"))
    )
    (net (code "97") (name "Net-(R3-Pad2)") (class "Default")
      (node (ref "R3") (pin "2") (pinfunction "2_2") (pintype "passive"))
      (node (ref "SV3") (pin "3") (pinfunction "3_3") (pintype "passive"))
    )
    (net (code "98") (name "Net-(R4-Pad2)") (class "Default")
      (node (ref "R4") (pin "2") (pinfunction "2_2") (pintype "passive"))
      (node (ref "SV3") (pin "4") (pinfunction "4_4") (pintype "passive"))
    )
    (net (code "99") (name "Net-(R5-Pad2)") (class "Default")
      (node (ref "R5") (pin "2") (pinfunction "2_2") (pintype "passive"))
      (node (ref "SV3") (pin "5") (pinfunction "5_5") (pintype "passive"))
    )
    (net (code "100") (name "Net-(R6-Pad2)") (class "Default")
      (node (ref "R6") (pin "2") (pinfunction "2_2") (pintype "passive"))
      (node (ref "SV3") (pin "6") (pinfunction "6_6") (pintype "passive"))
    )
    (net (code "101") (name "Net-(R7-Pad2)") (class "Default")
      (node (ref "R7") (pin "2") (pinfunction "2_2") (pintype "passive"))
      (node (ref "SV3") (pin "7") (pinfunction "7_7") (pintype "passive"))
    )
    (net (code "102") (name "Net-(R8-Pad2)") (class "Default")
      (node (ref "R8") (pin "2") (pinfunction "2_2") (pintype "passive"))
      (node (ref "SV3") (pin "8") (pinfunction "8_8") (pintype "passive"))
    )
    (net (code "103") (name "Net-(R11-Pad2)") (class "Default")
      (node (ref "R11") (pin "2") (pinfunction "2_2") (pintype "passive"))
      (node (ref "SV1") (pin "1") (pinfunction "1_1") (pintype "passive"))
    )
    (net (code "104") (name "Net-(R12-Pad2)") (class "Default")
      (node (ref "R12") (pin "2") (pinfunction "2_2") (pintype "passive"))
      (node (ref "SV1") (pin "2") (pinfunction "2_2") (pintype "passive"))
    )
    (net (code "105") (name "Net-(R13-Pad2)") (class "Default")
      (node (ref "R13") (pin "2") (pinfunction "2_2") (pintype "passive"))
      (node (ref "SV1") (pin "3") (pinfunction "3_3") (pintype "passive"))
    )
    (net (code "106") (name "Net-(R14-Pad2)") (class "Default")
      (node (ref "R14") (pin "2") (pinfunction "2_2") (pintype "passive"))
      (node (ref "SV1") (pin "4") (pinfunction "4_4") (pintype "passive"))
    )
    (net (code "107") (name "Net-(R15-Pad2)") (class "Default")
      (node (ref "R15") (pin "2") (pinfunction "2_2") (pintype "passive"))
      (node (ref "SV1") (pin "5") (pinfunction "5_5") (pintype "passive"))
    )
    (net (code "108") (name "Net-(R16-Pad2)") (class "Default")
      (node (ref "R16") (pin "2") (pinfunction "2_2") (pintype "passive"))
      (node (ref "SV1") (pin "6") (pinfunction "6_6") (pintype "passive"))
    )
    (net (code "109") (name "Net-(R17-Pad2)") (class "Default")
      (node (ref "R17") (pin "2") (pinfunction "2_2") (pintype "passive"))
      (node (ref "SV1") (pin "7") (pinfunction "7_7") (pintype "passive"))
    )
    (net (code "110") (name "Net-(R18-Pad2)") (class "Default")
      (node (ref "R18") (pin "2") (pinfunction "2_2") (pintype "passive"))
      (node (ref "SV1") (pin "8") (pinfunction "8_8") (pintype "passive"))
    )
    (net (code "111") (name "VCC") (class "Default")
      (node (ref "C1") (pin "1") (pinfunction "1_1") (pintype "passive"))
      (node (ref "C2") (pin "1") (pinfunction "1_1") (pintype "passive"))
      (node (ref "C9") (pin "+") (pinfunction "+_+") (pintype "passive"))
      (node (ref "IC1") (pin "19") (pinfunction "VCC_19") (pintype "power_in"))
      (node (ref "IC10") (pin "OUT") (pinfunction "OUT_OUT") (pintype "passive"))
      (node (ref "IC2") (pin "19") (pinfunction "VCC_19") (pintype "power_in"))
      (node (ref "R10") (pin "1") (pinfunction "1_1") (pintype "passive"))
      (node (ref "R20") (pin "1") (pinfunction "1_1") (pintype "passive"))
      (node (ref "SV6") (pin "5") (pinfunction "5_5") (pintype "passive"))
    )
    (net (code "112") (name "unconnected-(IC2-DOUT-Pad24)") (class "Default")
      (node (ref "IC2") (pin "24") (pinfunction "DOUT_24") (pintype "output"))
    )
    (net (code "113") (name "unconnected-(SV6-Pad1)") (class "Default")
      (node (ref "SV6") (pin "1") (pinfunction "1_1") (pintype "passive"))
    )
  )
)
